# Pump_Drive.net
KiCad netlist of a schematic drawn in Altium Designer
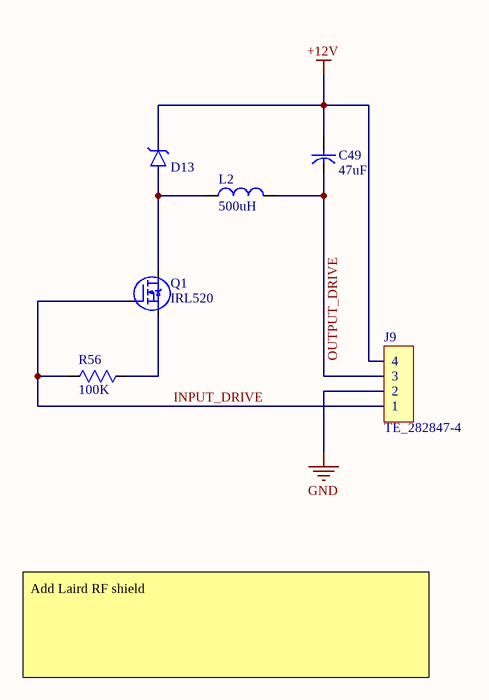
[diagram p0: Pump Drive.SchDoc]

(export (version "E")
  (design (tool "Eeschema 10.0.6"))
  (components
    (comp (ref "C49")
      (value "47uF")
      (description "EEE-1HA470XAP")
      (libsource (lib "Capacitors") (part "47uF_ECL_50V"))
    )
    (comp (ref "D13") (value "1A") (footprint "DO-41") (libsource (lib "Active") (part "IN4007 Power Diode")))
    (comp (ref "J9")
      (value "TE_282847-4")
      (footprint "TE 282847-4")
      (description "TB, TH, 4-Pos, 35Deg, 5.08mm")
      (fields
        (field (name "MANUFACTURER") "TE Connectivity AMP Connectors")
        (field (name "MANUFACTURER PART NUMBER") "282847-4")
      )
      (libsource (lib "Connectors") (part "TE_282847-4"))
    )
    (comp (ref "L2")
      (value "500uH")
      (description "1536Y")
      (libsource (lib "Inductors") (part "500uH_2A_THD"))
    )
    (comp (ref "Q1")
      (value "IRL520")
      (footprint "TO-220/3H")
      (description "Power MOSFET")
      (libsource (lib "VolcDB") (part "IRL540"))
    )
    (comp (ref "R56")
      (value "100K")
      (footprint "RESC14034X53N")
      (description "Res,SMD,10555,3W,5%")
      (libsource (lib "Resistors") (part "100k_10555_3W"))
    )
  )
  (nets
    (net (code "1") (name "+12V") (class "Default")
      (node (ref "C49") (pin "1") (pintype "passive"))
      (node (ref "D13") (pin "1") (pinfunction "1_1") (pintype "passive"))
      (node (ref "J9") (pin "4") (pinfunction "4_4") (pintype "passive"))
    )
    (net (code "2") (name "/INPUT_DRIVE") (class "Default")
      (node (ref "J9") (pin "1") (pinfunction "1_1") (pintype "passive"))
      (node (ref "Q1") (pin "1") (pinfunction "G_1") (pintype "passive"))
      (node (ref "R56") (pin "1") (pintype "passive"))
    )
    (net (code "3") (name "/OUTPUT_DRIVE") (class "Default")
      (node (ref "C49") (pin "2") (pintype "passive"))
      (node (ref "J9") (pin "3") (pinfunction "3_3") (pintype "passive"))
      (node (ref "L2") (pin "2") (pintype "passive"))
    )
    (net (code "4") (name "GND") (class "Default")
      (node (ref "J9") (pin "2") (pinfunction "2_2") (pintype "passive"))
    )
    (net (code "5") (name "Net-(Q1-D)") (class "Default")
      (node (ref "D13") (pin "2") (pinfunction "2_2") (pintype "passive"))
      (node (ref "L2") (pin "1") (pintype "passive"))
      (node (ref "Q1") (pin "2") (pinfunction "D_2") (pintype "passive"))
    )
    (net (code "6") (name "Net-(Q1-S)") (class "Default")
      (node (ref "Q1") (pin "3") (pinfunction "S_3") (pintype "passive"))
      (node (ref "R56") (pin "2") (pintype "passive"))
    )
  )
)
